# ASD2162.net
KiCad netlist of a schematic drawn in EAGLE
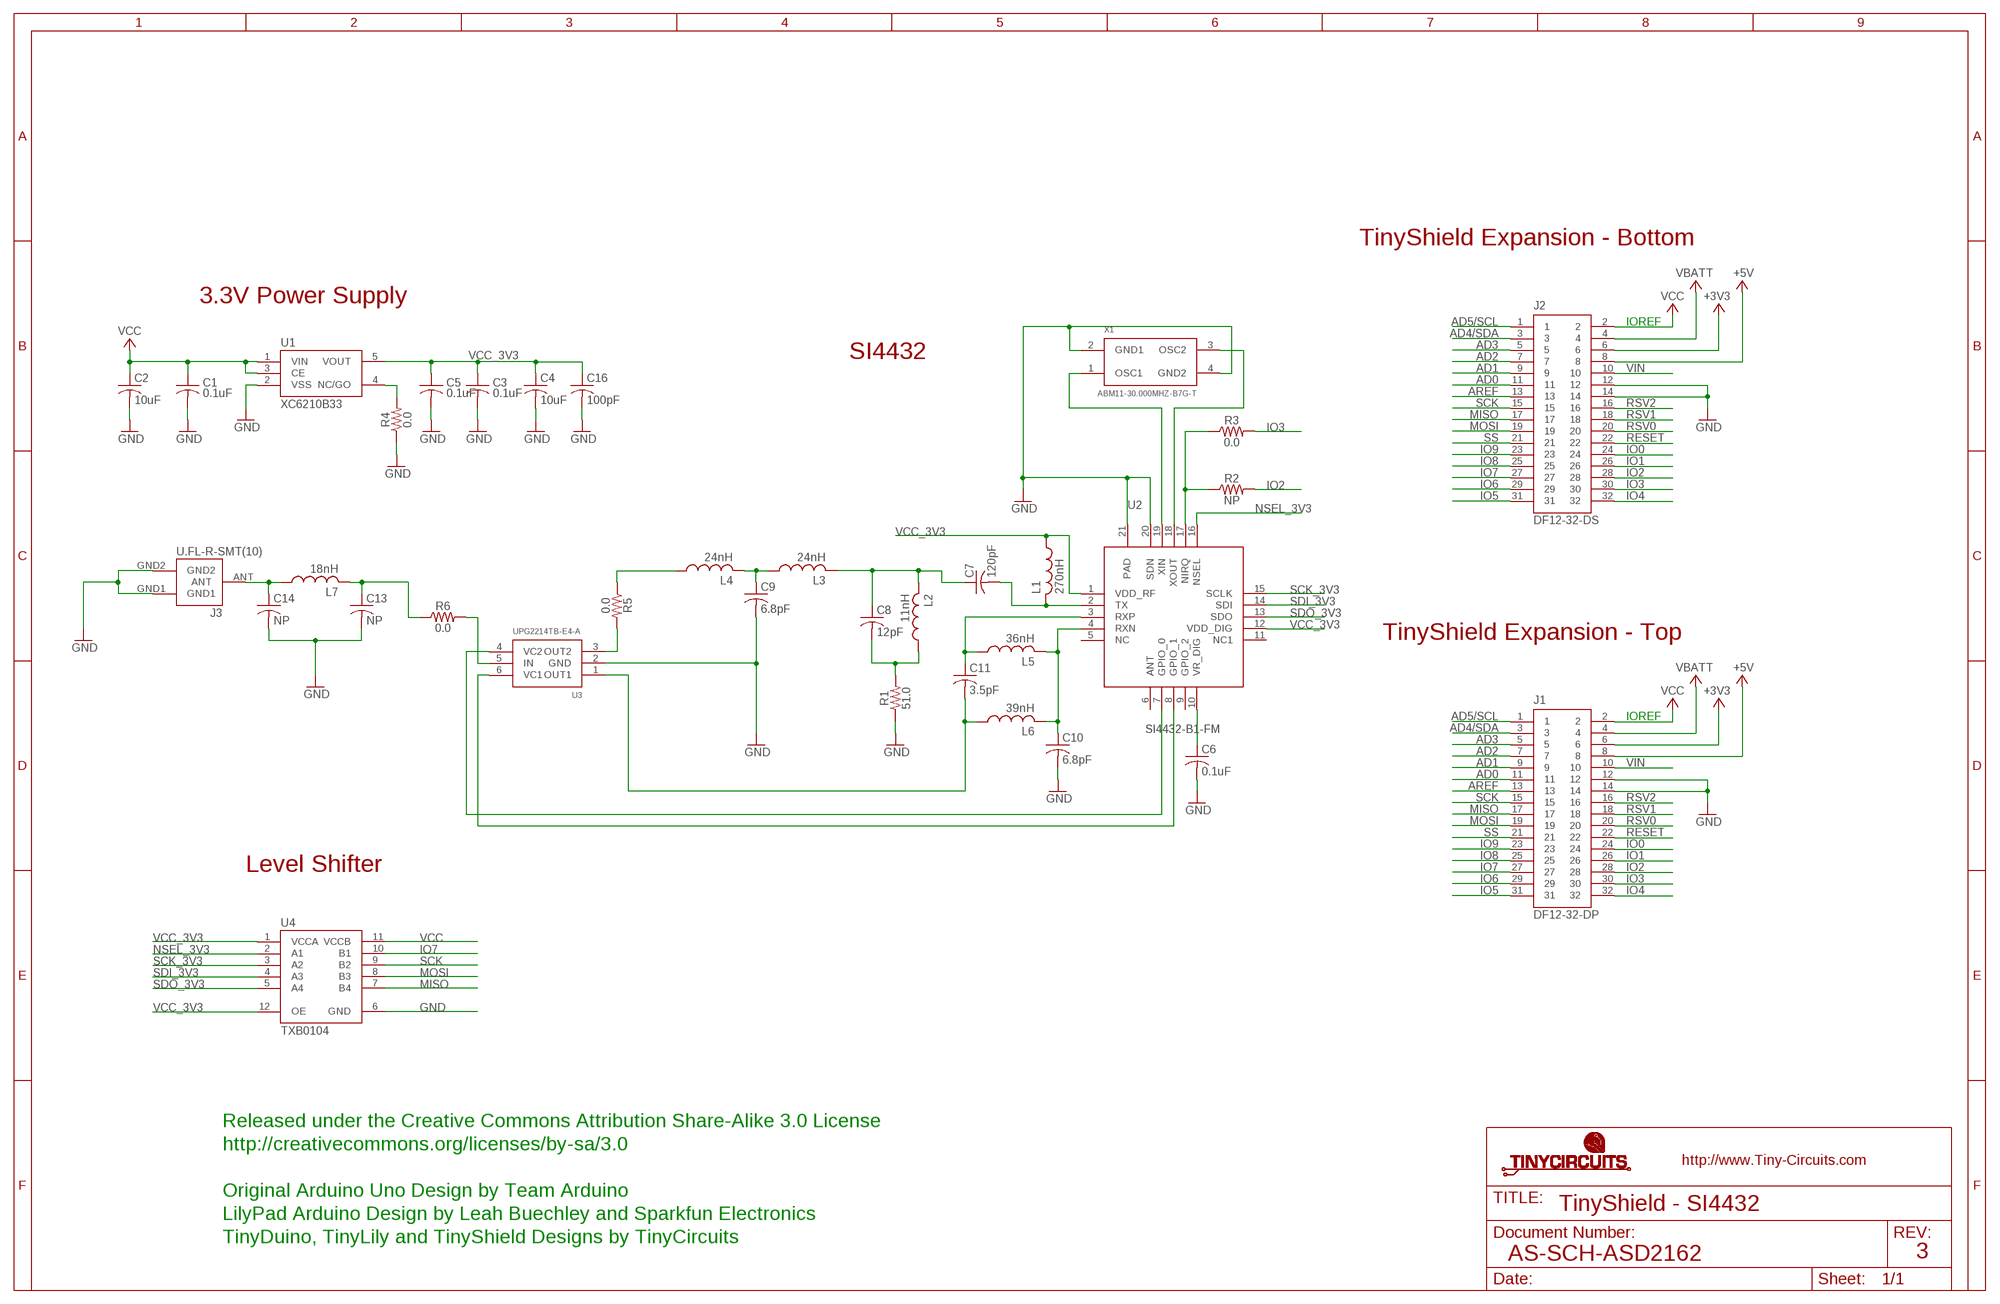
[diagram p0: schematic, sheet 1]

(export (version "E")
  (design (tool "Eeschema 10.0.6"))
  (components
    (comp (ref "C1")
      (value "0.1uF")
      (footprint "eagle-import:C0402")
      (fields (field (name "PARTNO") "AS-ITM-00008") (field (name "PARTNO_1") "AS-ITM-00008"))
      (libsource (lib "eagle-import") (part "AS-ITM-00008"))
    )
    (comp (ref "C2")
      (value "10uF")
      (footprint "eagle-import:C0805")
      (fields (field (name "PARTNO") "AS-ITM-00045") (field (name "PARTNO_1") "AS-ITM-00045"))
      (libsource (lib "eagle-import") (part "AS-ITM-00045"))
    )
    (comp (ref "C3")
      (value "0.1uF")
      (footprint "eagle-import:C0402")
      (fields (field (name "PARTNO") "AS-ITM-00008") (field (name "PARTNO_1") "AS-ITM-00008"))
      (libsource (lib "eagle-import") (part "AS-ITM-00008"))
    )
    (comp (ref "C4")
      (value "10uF")
      (footprint "eagle-import:C0805")
      (fields (field (name "PARTNO") "AS-ITM-00045") (field (name "PARTNO_1") "AS-ITM-00045"))
      (libsource (lib "eagle-import") (part "AS-ITM-00045"))
    )
    (comp (ref "C5")
      (value "0.1uF")
      (footprint "eagle-import:C0402")
      (fields (field (name "PARTNO") "AS-ITM-00008") (field (name "PARTNO_1") "AS-ITM-00008"))
      (libsource (lib "eagle-import") (part "AS-ITM-00008"))
    )
    (comp (ref "C6")
      (value "0.1uF")
      (footprint "eagle-import:C0402")
      (fields (field (name "PARTNO") "AS-ITM-00008") (field (name "PARTNO_1") "AS-ITM-00008"))
      (libsource (lib "eagle-import") (part "AS-ITM-00008"))
    )
    (comp (ref "C7")
      (value "120pF")
      (footprint "eagle-import:C0402")
      (fields (field (name "PARTNO") "AS-ITM-00251"))
      (libsource (lib "eagle-import") (part "AS-ITM-00251"))
    )
    (comp (ref "C8")
      (value "12pF")
      (footprint "eagle-import:C0402")
      (fields (field (name "PARTNO") "AS-ITM-00261") (field (name "PARTNO_1") "AS-ITM-00261"))
      (libsource (lib "eagle-import") (part "AS-ITM-00261"))
    )
    (comp (ref "C9")
      (value "6.8pF")
      (footprint "eagle-import:C0402")
      (fields (field (name "PARTNO") "AS-ITM-00252") (field (name "PARTNO_1") "AS-ITM-00252"))
      (libsource (lib "eagle-import") (part "AS-ITM-00252"))
    )
    (comp (ref "C10")
      (value "6.8pF")
      (footprint "eagle-import:C0402")
      (fields (field (name "PARTNO") "AS-ITM-00252") (field (name "PARTNO_1") "AS-ITM-00252"))
      (libsource (lib "eagle-import") (part "AS-ITM-00252"))
    )
    (comp (ref "C11")
      (value "3.5pF")
      (footprint "eagle-import:C0402")
      (fields (field (name "PARTNO") "AS-ITM-00258") (field (name "PARTNO_1") "AS-ITM-00258"))
      (libsource (lib "eagle-import") (part "AS-ITM-00258"))
    )
    (comp (ref "C13")
      (value "NP")
      (footprint "eagle-import:C0402")
      (fields (field (name "PARTNO") "AS-ITM-00084") (field (name "PARTNO_1") "AS-ITM-00084"))
      (libsource (lib "eagle-import") (part "AS-ITM-00084"))
    )
    (comp (ref "C14")
      (value "NP")
      (footprint "eagle-import:C0402")
      (fields (field (name "PARTNO") "AS-ITM-00084") (field (name "PARTNO_1") "AS-ITM-00084"))
      (libsource (lib "eagle-import") (part "AS-ITM-00084"))
    )
    (comp (ref "C16")
      (value "100pF")
      (footprint "eagle-import:0402")
      (fields (field (name "PARTNO") "AS-ITM-00148"))
      (libsource (lib "eagle-import") (part "AS-ITM-00148"))
    )
    (comp (ref "J1")
      (value "DF12-32-DP")
      (footprint "eagle-import:DF12-32-DP")
      (fields (field (name "PARTNO") "AS-ITM-00015") (field (name "PARTNO_1") "AS-ITM-00015"))
      (libsource (lib "eagle-import") (part "AS-ITM-00015"))
    )
    (comp (ref "J2")
      (value "DF12-32-DS")
      (footprint "eagle-import:DF12-32-DS")
      (fields (field (name "PARTNO") "AS-ITM-00012") (field (name "PARTNO_1") "AS-ITM-00012"))
      (libsource (lib "eagle-import") (part "AS-ITM-00012"))
    )
    (comp (ref "J3")
      (value "U.FL-R-SMT(10)")
      (footprint "eagle-import:U.FL-R-SMT(10)")
      (fields (field (name "PARTNO") "AS-ITM-00193"))
      (libsource (lib "eagle-import") (part "AS-ITM-00193"))
    )
    (comp (ref "L1")
      (value "270nH")
      (footprint "eagle-import:C0402")
      (fields (field (name "PARTNO") "AS-ITM-00250") (field (name "PARTNO_1") "AS-ITM-00250"))
      (libsource (lib "eagle-import") (part "AS-ITM-00250"))
    )
    (comp (ref "L2")
      (value "11nH")
      (footprint "eagle-import:C0402")
      (fields (field (name "PARTNO") "AS-ITM-00254") (field (name "PARTNO_1") "AS-ITM-00254"))
      (libsource (lib "eagle-import") (part "AS-ITM-00254"))
    )
    (comp (ref "L3")
      (value "24nH")
      (footprint "eagle-import:C0402")
      (fields (field (name "PARTNO") "AS-ITM-00257") (field (name "PARTNO_1") "AS-ITM-00257"))
      (libsource (lib "eagle-import") (part "AS-ITM-00257"))
    )
    (comp (ref "L4")
      (value "24nH")
      (footprint "eagle-import:C0402")
      (fields (field (name "PARTNO") "AS-ITM-00257") (field (name "PARTNO_1") "AS-ITM-00257"))
      (libsource (lib "eagle-import") (part "AS-ITM-00257"))
    )
    (comp (ref "L5")
      (value "36nH")
      (footprint "eagle-import:C0402")
      (fields (field (name "PARTNO") "AS-ITM-00253") (field (name "PARTNO_1") "AS-ITM-00253"))
      (libsource (lib "eagle-import") (part "AS-ITM-00253"))
    )
    (comp (ref "L6")
      (value "39nH")
      (footprint "eagle-import:C0402")
      (fields (field (name "PARTNO") "AS-ITM-00259") (field (name "PARTNO_1") "AS-ITM-00259"))
      (libsource (lib "eagle-import") (part "AS-ITM-00259"))
    )
    (comp (ref "L7")
      (value "18nH")
      (footprint "eagle-import:C0402")
      (fields (field (name "PARTNO") "AS-ITM-00260") (field (name "PARTNO_1") "AS-ITM-00260"))
      (libsource (lib "eagle-import") (part "AS-ITM-00260"))
    )
    (comp (ref "R1")
      (value "51.0")
      (footprint "eagle-import:0402")
      (fields (field (name "PARTNO") "AS-ITM-00262") (field (name "PARTNO_1") "AS-ITM-00262"))
      (libsource (lib "eagle-import") (part "AS-ITM-00262"))
    )
    (comp (ref "R2")
      (value "NP")
      (footprint "eagle-import:0402")
      (fields (field (name "PARTNO") "AS-ITM-00076"))
      (libsource (lib "eagle-import") (part "AS-ITM-00076"))
    )
    (comp (ref "R3")
      (value "0.0")
      (footprint "eagle-import:0402")
      (fields (field (name "PARTNO") "AS-ITM-00076"))
      (libsource (lib "eagle-import") (part "AS-ITM-00076"))
    )
    (comp (ref "R4")
      (value "0.0")
      (footprint "eagle-import:0402")
      (fields (field (name "PARTNO") "AS-ITM-00076"))
      (libsource (lib "eagle-import") (part "AS-ITM-00076"))
    )
    (comp (ref "R5")
      (value "0.0")
      (footprint "eagle-import:C0402")
      (fields (field (name "PARTNO") "AS-ITM-00076") (field (name "PARTNO_1") "AS-ITM-00076"))
      (libsource (lib "eagle-import") (part "AS-ITM-00076C0402"))
    )
    (comp (ref "R6")
      (value "0.0")
      (footprint "eagle-import:C0402")
      (fields (field (name "PARTNO") "AS-ITM-00076") (field (name "PARTNO_1") "AS-ITM-00076"))
      (libsource (lib "eagle-import") (part "AS-ITM-00076C0402"))
    )
    (comp (ref "U1")
      (value "XC6210B33")
      (footprint "eagle-import:SOT-25")
      (fields (field (name "PARTNO") "AS-ITM-00046"))
      (libsource (lib "eagle-import") (part "AS-ITM-00046"))
    )
    (comp (ref "U2")
      (value "SI4432-B1-FM")
      (footprint "eagle-import:QFN20")
      (fields (field (name "PARTNO") "AS-ITM-00194"))
      (libsource (lib "eagle-import") (part "AS-ITM-00194"))
    )
    (comp (ref "U3")
      (value "UPG2214TB-E4-A")
      (footprint "eagle-import:S06")
      (fields (field (name "PARTNO") "AS-ITM-00195"))
      (libsource (lib "eagle-import") (part "AS-ITM-00195"))
    )
    (comp (ref "U4")
      (value "TXB0104")
      (footprint "eagle-import:UQFN-12")
      (fields (field (name "PARTNO") "AS-ITM-00048"))
      (libsource (lib "eagle-import") (part "AS-ITM-00048"))
    )
    (comp (ref "X1")
      (value "ABM11-30.000MHZ-B7G-T")
      (footprint "eagle-import:ABM11")
      (fields (field (name "PARTNO") "AS-ITM-00199"))
      (libsource (lib "eagle-import") (part "AS-ITM-00199"))
    )
  )
  (nets
    (net (code "1") (name "+3V3") (class "Default")
      (node (ref "J1") (pin "6") (pinfunction "6_6") (pintype "bidirectional"))
      (node (ref "J2") (pin "6") (pinfunction "6_6") (pintype "bidirectional"))
    )
    (net (code "2") (name "+5V") (class "Default")
      (node (ref "J1") (pin "8") (pinfunction "8_8") (pintype "bidirectional"))
      (node (ref "J2") (pin "8") (pinfunction "8_8") (pintype "bidirectional"))
    )
    (net (code "3") (name "/AD0") (class "Default")
      (node (ref "J1") (pin "11") (pinfunction "11_11") (pintype "bidirectional"))
      (node (ref "J2") (pin "11") (pinfunction "11_11") (pintype "bidirectional"))
    )
    (net (code "4") (name "/AD1") (class "Default")
      (node (ref "J1") (pin "9") (pinfunction "9_9") (pintype "bidirectional"))
      (node (ref "J2") (pin "9") (pinfunction "9_9") (pintype "bidirectional"))
    )
    (net (code "5") (name "/AD2") (class "Default")
      (node (ref "J1") (pin "7") (pinfunction "7_7") (pintype "bidirectional"))
      (node (ref "J2") (pin "7") (pinfunction "7_7") (pintype "bidirectional"))
    )
    (net (code "6") (name "/AD3") (class "Default")
      (node (ref "J1") (pin "5") (pinfunction "5_5") (pintype "bidirectional"))
      (node (ref "J2") (pin "5") (pinfunction "5_5") (pintype "bidirectional"))
    )
    (net (code "7") (name "/AD4{slash}SDA") (class "Default")
      (node (ref "J1") (pin "3") (pinfunction "3_3") (pintype "bidirectional"))
      (node (ref "J2") (pin "3") (pinfunction "3_3") (pintype "bidirectional"))
    )
    (net (code "8") (name "/AD5{slash}SCL") (class "Default")
      (node (ref "J1") (pin "1") (pinfunction "1_1") (pintype "bidirectional"))
      (node (ref "J2") (pin "1") (pinfunction "1_1") (pintype "bidirectional"))
    )
    (net (code "9") (name "/AREF") (class "Default")
      (node (ref "J1") (pin "13") (pinfunction "13_13") (pintype "bidirectional"))
      (node (ref "J2") (pin "13") (pinfunction "13_13") (pintype "bidirectional"))
    )
    (net (code "10") (name "/IO0") (class "Default")
      (node (ref "J1") (pin "24") (pinfunction "24_24") (pintype "bidirectional"))
      (node (ref "J2") (pin "24") (pinfunction "24_24") (pintype "bidirectional"))
    )
    (net (code "11") (name "/IO1") (class "Default")
      (node (ref "J1") (pin "26") (pinfunction "26_26") (pintype "bidirectional"))
      (node (ref "J2") (pin "26") (pinfunction "26_26") (pintype "bidirectional"))
    )
    (net (code "12") (name "/IO2") (class "Default")
      (node (ref "J1") (pin "28") (pinfunction "28_28") (pintype "bidirectional"))
      (node (ref "J2") (pin "28") (pinfunction "28_28") (pintype "bidirectional"))
      (node (ref "R2") (pin "2") (pinfunction "2_2") (pintype "passive"))
    )
    (net (code "13") (name "/IO3") (class "Default")
      (node (ref "J1") (pin "30") (pinfunction "30_30") (pintype "bidirectional"))
      (node (ref "J2") (pin "30") (pinfunction "30_30") (pintype "bidirectional"))
      (node (ref "R3") (pin "2") (pinfunction "2_2") (pintype "passive"))
    )
    (net (code "14") (name "/IO4") (class "Default")
      (node (ref "J1") (pin "32") (pinfunction "32_32") (pintype "bidirectional"))
      (node (ref "J2") (pin "32") (pinfunction "32_32") (pintype "bidirectional"))
    )
    (net (code "15") (name "/IO5") (class "Default")
      (node (ref "J1") (pin "31") (pinfunction "31_31") (pintype "bidirectional"))
      (node (ref "J2") (pin "31") (pinfunction "31_31") (pintype "bidirectional"))
    )
    (net (code "16") (name "/IO6") (class "Default")
      (node (ref "J1") (pin "29") (pinfunction "29_29") (pintype "bidirectional"))
      (node (ref "J2") (pin "29") (pinfunction "29_29") (pintype "bidirectional"))
    )
    (net (code "17") (name "/IO7") (class "Default")
      (node (ref "J1") (pin "27") (pinfunction "27_27") (pintype "bidirectional"))
      (node (ref "J2") (pin "27") (pinfunction "27_27") (pintype "bidirectional"))
      (node (ref "U4") (pin "10") (pinfunction "B1_10") (pintype "bidirectional"))
    )
    (net (code "18") (name "/IO8") (class "Default")
      (node (ref "J1") (pin "25") (pinfunction "25_25") (pintype "bidirectional"))
      (node (ref "J2") (pin "25") (pinfunction "25_25") (pintype "bidirectional"))
    )
    (net (code "19") (name "/IO9") (class "Default")
      (node (ref "J1") (pin "23") (pinfunction "23_23") (pintype "bidirectional"))
      (node (ref "J2") (pin "23") (pinfunction "23_23") (pintype "bidirectional"))
    )
    (net (code "20") (name "/MISO") (class "Default")
      (node (ref "J1") (pin "17") (pinfunction "17_17") (pintype "bidirectional"))
      (node (ref "J2") (pin "17") (pinfunction "17_17") (pintype "bidirectional"))
      (node (ref "U4") (pin "7") (pinfunction "B4_7") (pintype "bidirectional"))
    )
    (net (code "21") (name "/MOSI") (class "Default")
      (node (ref "J1") (pin "19") (pinfunction "19_19") (pintype "bidirectional"))
      (node (ref "J2") (pin "19") (pinfunction "19_19") (pintype "bidirectional"))
      (node (ref "U4") (pin "8") (pinfunction "B3_8") (pintype "bidirectional"))
    )
    (net (code "22") (name "/NSEL_3V3") (class "Default")
      (node (ref "U2") (pin "16") (pinfunction "NSEL_16") (pintype "bidirectional"))
      (node (ref "U4") (pin "2") (pinfunction "A1_2") (pintype "bidirectional"))
    )
    (net (code "23") (name "/RESET") (class "Default")
      (node (ref "J1") (pin "22") (pinfunction "22_22") (pintype "bidirectional"))
      (node (ref "J2") (pin "22") (pinfunction "22_22") (pintype "bidirectional"))
    )
    (net (code "24") (name "/RSV0") (class "Default")
      (node (ref "J1") (pin "20") (pinfunction "20_20") (pintype "bidirectional"))
      (node (ref "J2") (pin "20") (pinfunction "20_20") (pintype "bidirectional"))
    )
    (net (code "25") (name "/RSV1") (class "Default")
      (node (ref "J1") (pin "18") (pinfunction "18_18") (pintype "bidirectional"))
      (node (ref "J2") (pin "18") (pinfunction "18_18") (pintype "bidirectional"))
    )
    (net (code "26") (name "/RSV2") (class "Default")
      (node (ref "J1") (pin "16") (pinfunction "16_16") (pintype "bidirectional"))
      (node (ref "J2") (pin "16") (pinfunction "16_16") (pintype "bidirectional"))
    )
    (net (code "27") (name "/SCK") (class "Default")
      (node (ref "J1") (pin "15") (pinfunction "15_15") (pintype "bidirectional"))
      (node (ref "J2") (pin "15") (pinfunction "15_15") (pintype "bidirectional"))
      (node (ref "U4") (pin "9") (pinfunction "B2_9") (pintype "bidirectional"))
    )
    (net (code "28") (name "/SCK_3V3") (class "Default")
      (node (ref "U2") (pin "15") (pinfunction "SCLK_15") (pintype "bidirectional"))
      (node (ref "U4") (pin "3") (pinfunction "A2_3") (pintype "bidirectional"))
    )
    (net (code "29") (name "/SDI_3V3") (class "Default")
      (node (ref "U2") (pin "14") (pinfunction "SDI_14") (pintype "bidirectional"))
      (node (ref "U4") (pin "4") (pinfunction "A3_4") (pintype "bidirectional"))
    )
    (net (code "30") (name "/SDO_3V3") (class "Default")
      (node (ref "U2") (pin "13") (pinfunction "SDO_13") (pintype "bidirectional"))
      (node (ref "U4") (pin "5") (pinfunction "A4_5") (pintype "bidirectional"))
    )
    (net (code "31") (name "/SS") (class "Default")
      (node (ref "J1") (pin "21") (pinfunction "21_21") (pintype "bidirectional"))
      (node (ref "J2") (pin "21") (pinfunction "21_21") (pintype "bidirectional"))
    )
    (net (code "32") (name "/VCC_3V3") (class "Default")
      (node (ref "C16") (pin "1") (pinfunction "1_1") (pintype "passive"))
      (node (ref "C3") (pin "1") (pinfunction "1_1") (pintype "passive"))
      (node (ref "C4") (pin "1") (pinfunction "1_1") (pintype "passive"))
      (node (ref "C5") (pin "1") (pinfunction "1_1") (pintype "passive"))
      (node (ref "L1") (pin "1") (pinfunction "1_1") (pintype "passive"))
      (node (ref "U1") (pin "5") (pinfunction "VOUT_5") (pintype "bidirectional"))
      (node (ref "U2") (pin "1") (pinfunction "VDD_RF_1") (pintype "bidirectional"))
      (node (ref "U2") (pin "12") (pinfunction "VDD_DIG_12") (pintype "bidirectional"))
      (node (ref "U4") (pin "1") (pinfunction "VCCA_1") (pintype "bidirectional"))
      (node (ref "U4") (pin "12") (pinfunction "OE_12") (pintype "bidirectional"))
    )
    (net (code "33") (name "/VIN") (class "Default")
      (node (ref "J1") (pin "10") (pinfunction "10_10") (pintype "bidirectional"))
      (node (ref "J2") (pin "10") (pinfunction "10_10") (pintype "bidirectional"))
    )
    (net (code "34") (name "GND") (class "Default")
      (node (ref "C1") (pin "2") (pinfunction "2_2") (pintype "passive"))
      (node (ref "C10") (pin "2") (pinfunction "2_2") (pintype "passive"))
      (node (ref "C13") (pin "2") (pinfunction "2_2") (pintype "passive"))
      (node (ref "C14") (pin "2") (pinfunction "2_2") (pintype "passive"))
      (node (ref "C16") (pin "2") (pinfunction "2_2") (pintype "passive"))
      (node (ref "C2") (pin "2") (pinfunction "2_2") (pintype "passive"))
      (node (ref "C3") (pin "2") (pinfunction "2_2") (pintype "passive"))
      (node (ref "C4") (pin "2") (pinfunction "2_2") (pintype "passive"))
      (node (ref "C5") (pin "2") (pinfunction "2_2") (pintype "passive"))
      (node (ref "C6") (pin "2") (pinfunction "2_2") (pintype "passive"))
      (node (ref "C9") (pin "2") (pinfunction "2_2") (pintype "passive"))
      (node (ref "J1") (pin "12") (pinfunction "12_12") (pintype "bidirectional"))
      (node (ref "J1") (pin "14") (pinfunction "14_14") (pintype "bidirectional"))
      (node (ref "J2") (pin "12") (pinfunction "12_12") (pintype "bidirectional"))
      (node (ref "J2") (pin "14") (pinfunction "14_14") (pintype "bidirectional"))
      (node (ref "J3") (pin "GND1") (pinfunction "GND1_GND1") (pintype "bidirectional"))
      (node (ref "J3") (pin "GND2") (pinfunction "GND2_GND2") (pintype "bidirectional"))
      (node (ref "R1") (pin "1") (pinfunction "1_1") (pintype "passive"))
      (node (ref "R4") (pin "1") (pinfunction "1_1") (pintype "passive"))
      (node (ref "U1") (pin "2") (pinfunction "VSS_2") (pintype "power_in"))
      (node (ref "U2") (pin "20") (pinfunction "SDN_20") (pintype "bidirectional"))
      (node (ref "U2") (pin "21") (pinfunction "PAD_21") (pintype "bidirectional"))
      (node (ref "U3") (pin "2") (pinfunction "GND_2") (pintype "bidirectional"))
      (node (ref "U4") (pin "6") (pinfunction "GND_6") (pintype "bidirectional"))
      (node (ref "X1") (pin "2") (pinfunction "GND1_2") (pintype "bidirectional"))
      (node (ref "X1") (pin "4") (pinfunction "GND2_4") (pintype "bidirectional"))
    )
    (net (code "35") (name "Net-(C7-Pad1)") (class "Default")
      (node (ref "C7") (pin "1") (pinfunction "1_1") (pintype "passive"))
      (node (ref "C8") (pin "1") (pinfunction "1_1") (pintype "passive"))
      (node (ref "L2") (pin "2") (pinfunction "2_2") (pintype "passive"))
      (node (ref "L3") (pin "2") (pinfunction "2_2") (pintype "passive"))
    )
    (net (code "36") (name "Net-(C8-Pad2)") (class "Default")
      (node (ref "C8") (pin "2") (pinfunction "2_2") (pintype "passive"))
      (node (ref "L2") (pin "1") (pinfunction "1_1") (pintype "passive"))
      (node (ref "R1") (pin "2") (pinfunction "2_2") (pintype "passive"))
    )
    (net (code "37") (name "Net-(C9-Pad1)") (class "Default")
      (node (ref "C9") (pin "1") (pinfunction "1_1") (pintype "passive"))
      (node (ref "L3") (pin "1") (pinfunction "1_1") (pintype "passive"))
      (node (ref "L4") (pin "2") (pinfunction "2_2") (pintype "passive"))
    )
    (net (code "38") (name "Net-(C13-Pad1)") (class "Default")
      (node (ref "C13") (pin "1") (pinfunction "1_1") (pintype "passive"))
      (node (ref "L7") (pin "2") (pinfunction "2_2") (pintype "passive"))
      (node (ref "R6") (pin "1") (pinfunction "1_1") (pintype "passive"))
    )
    (net (code "39") (name "Net-(C14-Pad1)") (class "Default")
      (node (ref "C14") (pin "1") (pinfunction "1_1") (pintype "passive"))
      (node (ref "J3") (pin "ANT") (pinfunction "ANT_ANT") (pintype "bidirectional"))
      (node (ref "L7") (pin "1") (pinfunction "1_1") (pintype "passive"))
    )
    (net (code "40") (name "Net-(L4-Pad1)") (class "Default")
      (node (ref "L4") (pin "1") (pinfunction "1_1") (pintype "passive"))
      (node (ref "R5") (pin "1") (pinfunction "1_1") (pintype "passive"))
    )
    (net (code "41") (name "Net-(U1-NC{slash}GO)") (class "Default")
      (node (ref "R4") (pin "2") (pinfunction "2_2") (pintype "passive"))
      (node (ref "U1") (pin "4") (pinfunction "NC/GO_4") (pintype "bidirectional"))
    )
    (net (code "42") (name "Net-(U2-GPIO_0)") (class "Default")
      (node (ref "U2") (pin "7") (pinfunction "GPIO_0_7") (pintype "bidirectional"))
      (node (ref "U3") (pin "4") (pinfunction "VC2_4") (pintype "bidirectional"))
    )
    (net (code "43") (name "Net-(U2-GPIO_1)") (class "Default")
      (node (ref "U2") (pin "8") (pinfunction "GPIO_1_8") (pintype "bidirectional"))
      (node (ref "U3") (pin "6") (pinfunction "VC1_6") (pintype "bidirectional"))
    )
    (net (code "44") (name "Net-(U2-NIRQ)") (class "Default")
      (node (ref "R2") (pin "1") (pinfunction "1_1") (pintype "passive"))
      (node (ref "R3") (pin "1") (pinfunction "1_1") (pintype "passive"))
      (node (ref "U2") (pin "17") (pinfunction "NIRQ_17") (pintype "bidirectional"))
    )
    (net (code "45") (name "Net-(U2-RXN)") (class "Default")
      (node (ref "C10") (pin "1") (pinfunction "1_1") (pintype "passive"))
      (node (ref "L5") (pin "2") (pinfunction "2_2") (pintype "passive"))
      (node (ref "L6") (pin "2") (pinfunction "2_2") (pintype "passive"))
      (node (ref "U2") (pin "4") (pinfunction "RXN_4") (pintype "bidirectional"))
    )
    (net (code "46") (name "Net-(U2-RXP)") (class "Default")
      (node (ref "C11") (pin "1") (pinfunction "1_1") (pintype "passive"))
      (node (ref "L5") (pin "1") (pinfunction "1_1") (pintype "passive"))
      (node (ref "U2") (pin "3") (pinfunction "RXP_3") (pintype "bidirectional"))
    )
    (net (code "47") (name "Net-(U2-TX)") (class "Default")
      (node (ref "C7") (pin "2") (pinfunction "2_2") (pintype "passive"))
      (node (ref "L1") (pin "2") (pinfunction "2_2") (pintype "passive"))
      (node (ref "U2") (pin "2") (pinfunction "TX_2") (pintype "bidirectional"))
    )
    (net (code "48") (name "Net-(U2-VR_DIG)") (class "Default")
      (node (ref "C6") (pin "1") (pinfunction "1_1") (pintype "passive"))
      (node (ref "U2") (pin "10") (pinfunction "VR_DIG_10") (pintype "bidirectional"))
    )
    (net (code "49") (name "Net-(U2-XIN)") (class "Default")
      (node (ref "U2") (pin "19") (pinfunction "XIN_19") (pintype "bidirectional"))
      (node (ref "X1") (pin "1") (pinfunction "OSC1_1") (pintype "bidirectional"))
    )
    (net (code "50") (name "Net-(U2-XOUT)") (class "Default")
      (node (ref "U2") (pin "18") (pinfunction "XOUT_18") (pintype "bidirectional"))
      (node (ref "X1") (pin "3") (pinfunction "OSC2_3") (pintype "bidirectional"))
    )
    (net (code "51") (name "Net-(U3-IN)") (class "Default")
      (node (ref "R6") (pin "2") (pinfunction "2_2") (pintype "passive"))
      (node (ref "U3") (pin "5") (pinfunction "IN_5") (pintype "bidirectional"))
    )
    (net (code "52") (name "Net-(U3-OUT1)") (class "Default")
      (node (ref "C11") (pin "2") (pinfunction "2_2") (pintype "passive"))
      (node (ref "L6") (pin "1") (pinfunction "1_1") (pintype "passive"))
      (node (ref "U3") (pin "1") (pinfunction "OUT1_1") (pintype "bidirectional"))
    )
    (net (code "53") (name "Net-(U3-OUT2)") (class "Default")
      (node (ref "R5") (pin "2") (pinfunction "2_2") (pintype "passive"))
      (node (ref "U3") (pin "3") (pinfunction "OUT2_3") (pintype "bidirectional"))
    )
    (net (code "54") (name "VBATT") (class "Default")
      (node (ref "J1") (pin "4") (pinfunction "4_4") (pintype "bidirectional"))
      (node (ref "J2") (pin "4") (pinfunction "4_4") (pintype "bidirectional"))
    )
    (net (code "55") (name "VCC") (class "Default")
      (node (ref "C1") (pin "1") (pinfunction "1_1") (pintype "passive"))
      (node (ref "C2") (pin "1") (pinfunction "1_1") (pintype "passive"))
      (node (ref "J1") (pin "2") (pinfunction "2_2") (pintype "bidirectional"))
      (node (ref "J2") (pin "2") (pinfunction "2_2") (pintype "bidirectional"))
      (node (ref "U1") (pin "1") (pinfunction "VIN_1") (pintype "bidirectional"))
      (node (ref "U1") (pin "3") (pinfunction "CE_3") (pintype "bidirectional"))
      (node (ref "U4") (pin "11") (pinfunction "VCCB_11") (pintype "bidirectional"))
    )
    (net (code "56") (name "unconnected-(U2-ANT-Pad6)") (class "Default")
      (node (ref "U2") (pin "6") (pinfunction "ANT_6") (pintype "bidirectional"))
    )
    (net (code "57") (name "unconnected-(U2-GPIO_2-Pad9)") (class "Default")
      (node (ref "U2") (pin "9") (pinfunction "GPIO_2_9") (pintype "bidirectional"))
    )
    (net (code "58") (name "unconnected-(U2-NC-Pad5)") (class "Default")
      (node (ref "U2") (pin "5") (pinfunction "NC_5") (pintype "bidirectional"))
    )
    (net (code "59") (name "unconnected-(U2-NC1-Pad11)") (class "Default")
      (node (ref "U2") (pin "11") (pinfunction "NC1_11") (pintype "bidirectional"))
    )
  )
)
